# mainboard.net
KiCad netlist of a schematic drawn in EAGLE
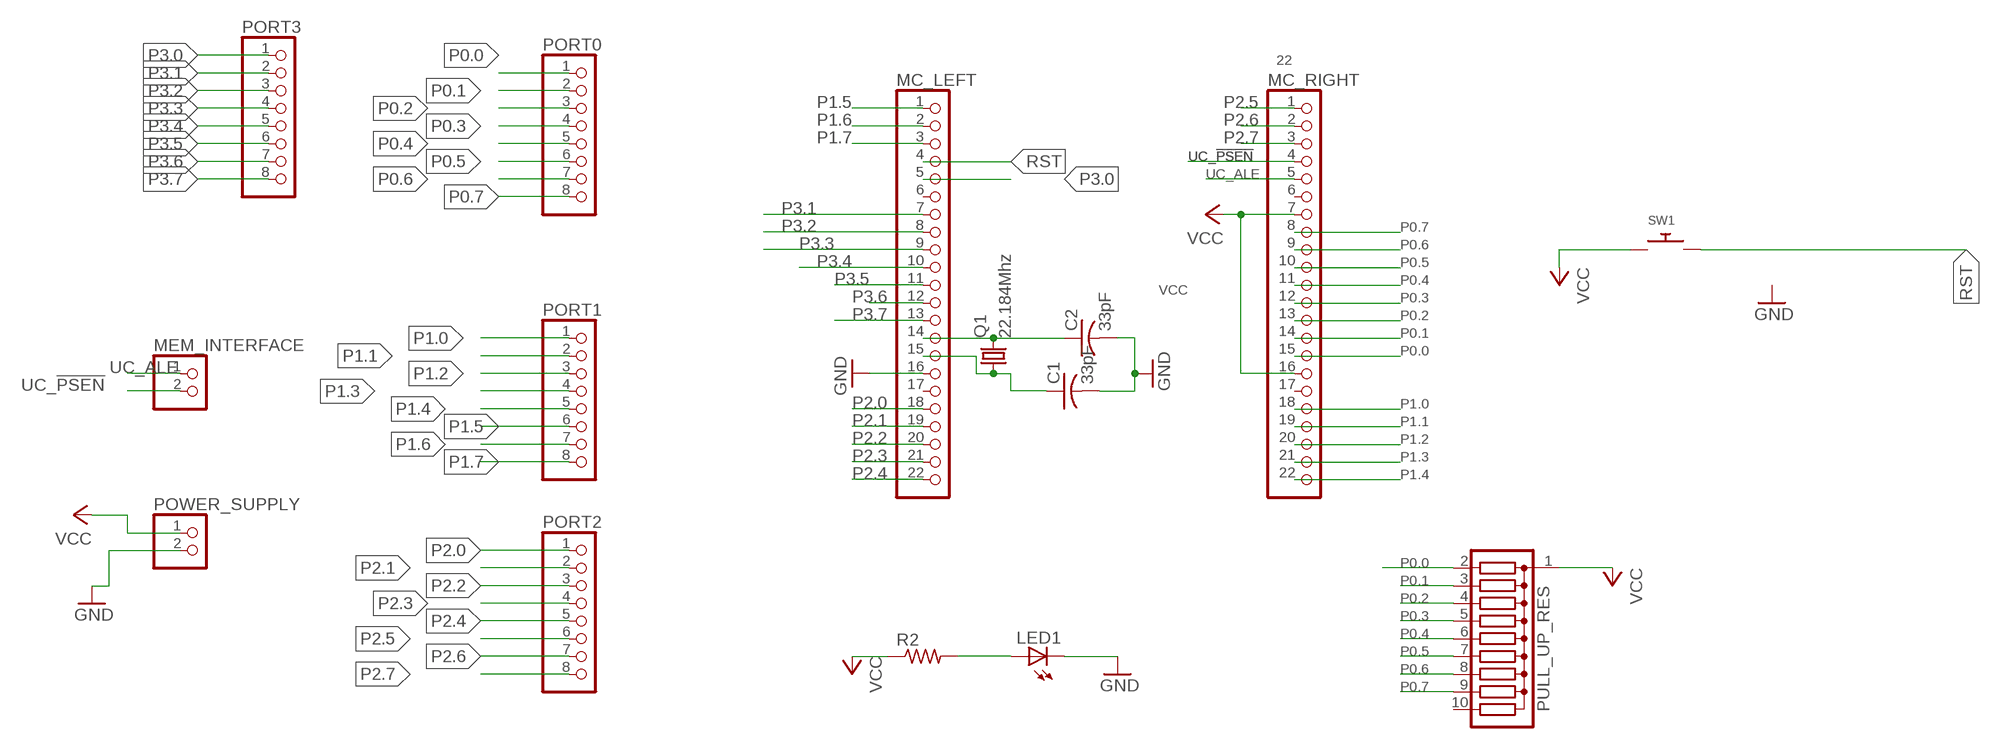
[diagram p0: schematic, sheet 1]

(export (version "E")
  (design (tool "Eeschema 10.0.6"))
  (components
    (comp (ref "C1")
      (value "33pF")
      (footprint "eagle-import:C050-025X075")
      (libsource (lib "eagle-import") (part "C-US050-025X075"))
    )
    (comp (ref "C2")
      (value "33pF")
      (footprint "eagle-import:C050-025X075")
      (libsource (lib "eagle-import") (part "C-US050-025X075"))
    )
    (comp (ref "LED1")
      (value "LED3MM")
      (footprint "eagle-import:LED3MM")
      (libsource (lib "eagle-import") (part "LED3MM"))
    )
    (comp (ref "MC_LEFT")
      (value "PINHD-1X22")
      (footprint "eagle-import:1X22")
      (libsource (lib "eagle-import") (part "PINHD-1X22"))
    )
    (comp (ref "MC_RIGHT")
      (value "PINHD-1X22")
      (footprint "eagle-import:1X22")
      (libsource (lib "eagle-import") (part "PINHD-1X22"))
    )
    (comp (ref "MEM_INTERFACE")
      (value "PINHD-1X2")
      (footprint "eagle-import:1X02")
      (libsource (lib "eagle-import") (part "PINHD-1X2"))
    )
    (comp (ref "PORT0")
      (value "PINHD-1X8")
      (footprint "eagle-import:1X08")
      (libsource (lib "eagle-import") (part "PINHD-1X8"))
    )
    (comp (ref "PORT1")
      (value "PINHD-1X8")
      (footprint "eagle-import:1X08")
      (libsource (lib "eagle-import") (part "PINHD-1X8"))
    )
    (comp (ref "PORT2")
      (value "PINHD-1X8")
      (footprint "eagle-import:1X08")
      (libsource (lib "eagle-import") (part "PINHD-1X8"))
    )
    (comp (ref "PORT3")
      (value "PINHD-1X8")
      (footprint "eagle-import:1X08")
      (libsource (lib "eagle-import") (part "PINHD-1X8"))
    )
    (comp (ref "POWER_SUPPLY")
      (value "PINHD-1X2")
      (footprint "eagle-import:1X02")
      (libsource (lib "eagle-import") (part "PINHD-1X2"))
    )
    (comp (ref "PULL_UP_RES")
      (value "G09R")
      (footprint "eagle-import:SIL10")
      (libsource (lib "eagle-import") (part "G09R"))
    )
    (comp (ref "Q1")
      (value "22.184Mhz")
      (footprint "eagle-import:HC49_S")
      (libsource (lib "eagle-import") (part "CRYSTALHC49S"))
    )
    (comp (ref "R2")
      (value "R-US_0204/5")
      (footprint "eagle-import:0204_5")
      (libsource (lib "eagle-import") (part "R-US_0204/5"))
    )
    (comp (ref "SW1")
      (value "SWITCH_PUSHBUTTONEVQ-PE")
      (footprint "eagle-import:TACT_PANA-EVQ")
      (libsource (lib "eagle-import") (part "SWITCH_PUSHBUTTONEVQ-PE"))
    )
  )
  (nets
    (net (code "1") (name "/UC_ALE") (class "Default")
      (node (ref "MC_RIGHT") (pin "5") (pinfunction "5_5") (pintype "passive"))
      (node (ref "MEM_INTERFACE") (pin "1") (pinfunction "1_1") (pintype "passive"))
    )
    (net (code "2") (name "/UC_~{PSEN}") (class "Default")
      (node (ref "MC_RIGHT") (pin "4") (pinfunction "4_4") (pintype "passive"))
      (node (ref "MEM_INTERFACE") (pin "2") (pinfunction "2_2") (pintype "passive"))
    )
    (net (code "3") (name "GND") (class "Default")
      (node (ref "C1") (pin "2") (pinfunction "2_2") (pintype "passive"))
      (node (ref "C2") (pin "2") (pinfunction "2_2") (pintype "passive"))
      (node (ref "LED1") (pin "K") (pinfunction "C_K") (pintype "passive"))
      (node (ref "MC_LEFT") (pin "16") (pinfunction "16_16") (pintype "passive"))
      (node (ref "POWER_SUPPLY") (pin "2") (pinfunction "2_2") (pintype "passive"))
    )
    (net (code "4") (name "Net-(C1-Pad1)") (class "Default")
      (node (ref "C1") (pin "1") (pinfunction "1_1") (pintype "passive"))
      (node (ref "MC_LEFT") (pin "15") (pinfunction "15_15") (pintype "passive"))
      (node (ref "Q1") (pin "1") (pinfunction "1_1") (pintype "passive"))
    )
    (net (code "5") (name "Net-(C2-Pad1)") (class "Default")
      (node (ref "C2") (pin "1") (pinfunction "1_1") (pintype "passive"))
      (node (ref "MC_LEFT") (pin "14") (pinfunction "14_14") (pintype "passive"))
      (node (ref "Q1") (pin "2") (pinfunction "2_2") (pintype "passive"))
    )
    (net (code "6") (name "Net-(LED1-PadA)") (class "Default")
      (node (ref "LED1") (pin "A") (pinfunction "A_A") (pintype "passive"))
      (node (ref "R2") (pin "2") (pinfunction "2_2") (pintype "passive"))
    )
    (net (code "7") (name "P0.0") (class "Default")
      (node (ref "MC_RIGHT") (pin "15") (pinfunction "15_15") (pintype "passive"))
      (node (ref "PORT0") (pin "1") (pinfunction "1_1") (pintype "passive"))
      (node (ref "PULL_UP_RES") (pin "2") (pinfunction "2_2") (pintype "passive"))
    )
    (net (code "8") (name "P0.1") (class "Default")
      (node (ref "MC_RIGHT") (pin "14") (pinfunction "14_14") (pintype "passive"))
      (node (ref "PORT0") (pin "2") (pinfunction "2_2") (pintype "passive"))
      (node (ref "PULL_UP_RES") (pin "3") (pinfunction "3_3") (pintype "passive"))
    )
    (net (code "9") (name "P0.2") (class "Default")
      (node (ref "MC_RIGHT") (pin "13") (pinfunction "13_13") (pintype "passive"))
      (node (ref "PORT0") (pin "3") (pinfunction "3_3") (pintype "passive"))
      (node (ref "PULL_UP_RES") (pin "4") (pinfunction "4_4") (pintype "passive"))
    )
    (net (code "10") (name "P0.3") (class "Default")
      (node (ref "MC_RIGHT") (pin "12") (pinfunction "12_12") (pintype "passive"))
      (node (ref "PORT0") (pin "4") (pinfunction "4_4") (pintype "passive"))
      (node (ref "PULL_UP_RES") (pin "5") (pinfunction "5_5") (pintype "passive"))
    )
    (net (code "11") (name "P0.4") (class "Default")
      (node (ref "MC_RIGHT") (pin "11") (pinfunction "11_11") (pintype "passive"))
      (node (ref "PORT0") (pin "5") (pinfunction "5_5") (pintype "passive"))
      (node (ref "PULL_UP_RES") (pin "6") (pinfunction "6_6") (pintype "passive"))
    )
    (net (code "12") (name "P0.5") (class "Default")
      (node (ref "MC_RIGHT") (pin "10") (pinfunction "10_10") (pintype "passive"))
      (node (ref "PORT0") (pin "6") (pinfunction "6_6") (pintype "passive"))
      (node (ref "PULL_UP_RES") (pin "7") (pinfunction "7_7") (pintype "passive"))
    )
    (net (code "13") (name "P0.6") (class "Default")
      (node (ref "MC_RIGHT") (pin "9") (pinfunction "9_9") (pintype "passive"))
      (node (ref "PORT0") (pin "7") (pinfunction "7_7") (pintype "passive"))
      (node (ref "PULL_UP_RES") (pin "8") (pinfunction "8_8") (pintype "passive"))
    )
    (net (code "14") (name "P0.7") (class "Default")
      (node (ref "MC_RIGHT") (pin "8") (pinfunction "8_8") (pintype "passive"))
      (node (ref "PORT0") (pin "8") (pinfunction "8_8") (pintype "passive"))
      (node (ref "PULL_UP_RES") (pin "9") (pinfunction "9_9") (pintype "passive"))
    )
    (net (code "15") (name "P1.0") (class "Default")
      (node (ref "MC_RIGHT") (pin "18") (pinfunction "18_18") (pintype "passive"))
      (node (ref "PORT1") (pin "1") (pinfunction "1_1") (pintype "passive"))
    )
    (net (code "16") (name "P1.1") (class "Default")
      (node (ref "MC_RIGHT") (pin "19") (pinfunction "19_19") (pintype "passive"))
      (node (ref "PORT1") (pin "2") (pinfunction "2_2") (pintype "passive"))
    )
    (net (code "17") (name "P1.2") (class "Default")
      (node (ref "MC_RIGHT") (pin "20") (pinfunction "20_20") (pintype "passive"))
      (node (ref "PORT1") (pin "3") (pinfunction "3_3") (pintype "passive"))
    )
    (net (code "18") (name "P1.3") (class "Default")
      (node (ref "MC_RIGHT") (pin "21") (pinfunction "21_21") (pintype "passive"))
      (node (ref "PORT1") (pin "4") (pinfunction "4_4") (pintype "passive"))
    )
    (net (code "19") (name "P1.4") (class "Default")
      (node (ref "MC_RIGHT") (pin "22") (pinfunction "22_22") (pintype "passive"))
      (node (ref "PORT1") (pin "5") (pinfunction "5_5") (pintype "passive"))
    )
    (net (code "20") (name "P1.5") (class "Default")
      (node (ref "MC_LEFT") (pin "1") (pinfunction "1_1") (pintype "passive"))
      (node (ref "PORT1") (pin "6") (pinfunction "6_6") (pintype "passive"))
    )
    (net (code "21") (name "P1.6") (class "Default")
      (node (ref "MC_LEFT") (pin "2") (pinfunction "2_2") (pintype "passive"))
      (node (ref "PORT1") (pin "7") (pinfunction "7_7") (pintype "passive"))
    )
    (net (code "22") (name "P1.7") (class "Default")
      (node (ref "MC_LEFT") (pin "3") (pinfunction "3_3") (pintype "passive"))
      (node (ref "PORT1") (pin "8") (pinfunction "8_8") (pintype "passive"))
    )
    (net (code "23") (name "P2.0") (class "Default")
      (node (ref "MC_LEFT") (pin "18") (pinfunction "18_18") (pintype "passive"))
      (node (ref "PORT2") (pin "1") (pinfunction "1_1") (pintype "passive"))
    )
    (net (code "24") (name "P2.1") (class "Default")
      (node (ref "MC_LEFT") (pin "19") (pinfunction "19_19") (pintype "passive"))
      (node (ref "PORT2") (pin "2") (pinfunction "2_2") (pintype "passive"))
    )
    (net (code "25") (name "P2.2") (class "Default")
      (node (ref "MC_LEFT") (pin "20") (pinfunction "20_20") (pintype "passive"))
      (node (ref "PORT2") (pin "3") (pinfunction "3_3") (pintype "passive"))
    )
    (net (code "26") (name "P2.3") (class "Default")
      (node (ref "MC_LEFT") (pin "21") (pinfunction "21_21") (pintype "passive"))
      (node (ref "PORT2") (pin "4") (pinfunction "4_4") (pintype "passive"))
    )
    (net (code "27") (name "P2.4") (class "Default")
      (node (ref "MC_LEFT") (pin "22") (pinfunction "22_22") (pintype "passive"))
      (node (ref "PORT2") (pin "5") (pinfunction "5_5") (pintype "passive"))
    )
    (net (code "28") (name "P2.5") (class "Default")
      (node (ref "MC_RIGHT") (pin "1") (pinfunction "1_1") (pintype "passive"))
      (node (ref "PORT2") (pin "6") (pinfunction "6_6") (pintype "passive"))
    )
    (net (code "29") (name "P2.6") (class "Default")
      (node (ref "MC_RIGHT") (pin "2") (pinfunction "2_2") (pintype "passive"))
      (node (ref "PORT2") (pin "7") (pinfunction "7_7") (pintype "passive"))
    )
    (net (code "30") (name "P2.7") (class "Default")
      (node (ref "MC_RIGHT") (pin "3") (pinfunction "3_3") (pintype "passive"))
      (node (ref "PORT2") (pin "8") (pinfunction "8_8") (pintype "passive"))
    )
    (net (code "31") (name "P3.0") (class "Default")
      (node (ref "MC_LEFT") (pin "5") (pinfunction "5_5") (pintype "passive"))
      (node (ref "PORT3") (pin "1") (pinfunction "1_1") (pintype "passive"))
    )
    (net (code "32") (name "P3.1") (class "Default")
      (node (ref "MC_LEFT") (pin "7") (pinfunction "7_7") (pintype "passive"))
      (node (ref "PORT3") (pin "2") (pinfunction "2_2") (pintype "passive"))
    )
    (net (code "33") (name "P3.2") (class "Default")
      (node (ref "MC_LEFT") (pin "8") (pinfunction "8_8") (pintype "passive"))
      (node (ref "PORT3") (pin "3") (pinfunction "3_3") (pintype "passive"))
    )
    (net (code "34") (name "P3.3") (class "Default")
      (node (ref "MC_LEFT") (pin "9") (pinfunction "9_9") (pintype "passive"))
      (node (ref "PORT3") (pin "4") (pinfunction "4_4") (pintype "passive"))
    )
    (net (code "35") (name "P3.4") (class "Default")
      (node (ref "MC_LEFT") (pin "10") (pinfunction "10_10") (pintype "passive"))
      (node (ref "PORT3") (pin "5") (pinfunction "5_5") (pintype "passive"))
    )
    (net (code "36") (name "P3.5") (class "Default")
      (node (ref "MC_LEFT") (pin "11") (pinfunction "11_11") (pintype "passive"))
      (node (ref "PORT3") (pin "6") (pinfunction "6_6") (pintype "passive"))
    )
    (net (code "37") (name "P3.6") (class "Default")
      (node (ref "MC_LEFT") (pin "12") (pinfunction "12_12") (pintype "passive"))
      (node (ref "PORT3") (pin "7") (pinfunction "7_7") (pintype "passive"))
    )
    (net (code "38") (name "P3.7") (class "Default")
      (node (ref "MC_LEFT") (pin "13") (pinfunction "13_13") (pintype "passive"))
      (node (ref "PORT3") (pin "8") (pinfunction "8_8") (pintype "passive"))
    )
    (net (code "39") (name "RST") (class "Default")
      (node (ref "MC_LEFT") (pin "4") (pinfunction "4_4") (pintype "passive"))
      (node (ref "SW1") (pin "P$2") (pinfunction "P$2_P$2") (pintype "passive"))
    )
    (net (code "40") (name "VCC") (class "Default")
      (node (ref "MC_RIGHT") (pin "16") (pinfunction "16_16") (pintype "passive"))
      (node (ref "MC_RIGHT") (pin "7") (pinfunction "7_7") (pintype "passive"))
      (node (ref "POWER_SUPPLY") (pin "1") (pinfunction "1_1") (pintype "passive"))
      (node (ref "PULL_UP_RES") (pin "1") (pinfunction "1_1") (pintype "passive"))
      (node (ref "R2") (pin "1") (pinfunction "1_1") (pintype "passive"))
      (node (ref "SW1") (pin "P$1") (pinfunction "P$1_P$1") (pintype "passive"))
    )
    (net (code "41") (name "unconnected-(MC_LEFT-Pad6)") (class "Default")
      (node (ref "MC_LEFT") (pin "6") (pinfunction "6_6") (pintype "passive"))
    )
    (net (code "42") (name "unconnected-(MC_LEFT-Pad17)") (class "Default")
      (node (ref "MC_LEFT") (pin "17") (pinfunction "17_17") (pintype "passive"))
    )
    (net (code "43") (name "unconnected-(MC_RIGHT-Pad6)") (class "Default")
      (node (ref "MC_RIGHT") (pin "6") (pinfunction "6_6") (pintype "passive"))
    )
    (net (code "44") (name "unconnected-(MC_RIGHT-Pad17)") (class "Default")
      (node (ref "MC_RIGHT") (pin "17") (pinfunction "17_17") (pintype "passive"))
    )
    (net (code "45") (name "unconnected-(PULL_UP_RES-Pad10)") (class "Default")
      (node (ref "PULL_UP_RES") (pin "10") (pinfunction "10_10") (pintype "passive"))
    )
  )
)
